# MouseSensor.net
KiCad netlist of a schematic drawn in Altium Designer
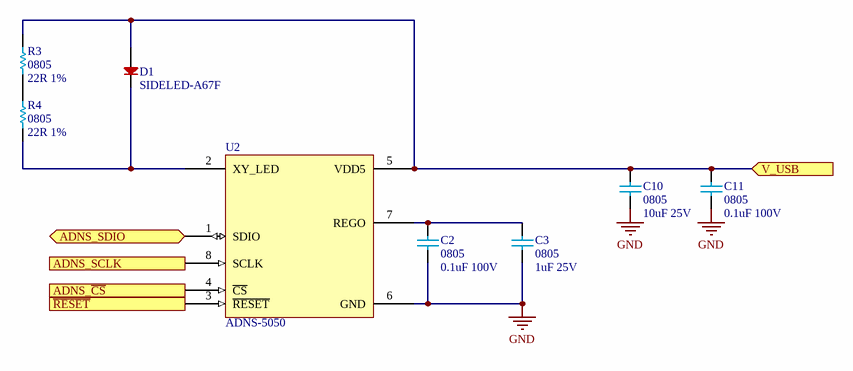
[diagram p0: MouseSensor.SchDoc]

(export (version "E")
  (design (tool "Eeschema 10.0.6"))
  (components
    (comp (ref "C2")
      (value "0805")
      (footprint "0805 - TALL")
      (description "0805, X5R or better")
      (fields (field (name "ALTIUM_VALUE") "0.1uF 100V"))
      (libsource (lib "Chip_Passives") (part "Cap 0.1uF 100V"))
    )
    (comp (ref "C3")
      (value "0805")
      (footprint "0805 - TALL")
      (description "0805, X5R or better")
      (fields (field (name "ALTIUM_VALUE") "1uF 25V"))
      (libsource (lib "Chip_Passives") (part "Cap 1uF 25V"))
    )
    (comp (ref "C10")
      (value "0805")
      (footprint "0805 - TALL")
      (description "0805, X5R or better")
      (fields (field (name "ALTIUM_VALUE") "10uF 25V"))
      (libsource (lib "Chip_Passives") (part "Cap 10uF 25V"))
    )
    (comp (ref "C11")
      (value "0805")
      (footprint "0805 - TALL")
      (description "0805, X5R or better")
      (fields (field (name "ALTIUM_VALUE") "0.1uF 100V"))
      (libsource (lib "Chip_Passives") (part "Cap 0.1uF 100V"))
    )
    (comp (ref "D1")
      (value "SIDELED-A67F")
      (footprint "SIDELED-A67F")
      (description "Red/Orange/Yellow Side-facing SMT LEDs, high brightness (~2lm)")
      (libsource (lib "LEDs") (part "SIDELED-A67F"))
    )
    (comp (ref "R3")
      (value "0805")
      (footprint "0805")
      (description "Chip resistor")
      (fields (field (name "ALTIUM_VALUE") "22R 1%"))
      (libsource (lib "Chip_Passives") (part "Res 22R 1% 0805"))
    )
    (comp (ref "R4")
      (value "0805")
      (footprint "0805")
      (description "Chip resistor")
      (fields (field (name "ALTIUM_VALUE") "22R 1%"))
      (libsource (lib "Chip_Passives") (part "Res 22R 1% 0805"))
    )
    (comp (ref "U2")
      (value "ADNS-5050")
      (footprint "ADNS-5050")
      (description "Optical Mouse Navigation Sensor")
      (libsource (lib "OptoElectronics") (part "ADNS-5050"))
    )
  )
  (nets
    (net (code "1") (name "/ADNS_SCLK") (class "Default")
      (node (ref "U2") (pin "8") (pinfunction "SCLK_8") (pintype "input"))
    )
    (net (code "2") (name "/ADNS_SDIO") (class "Default")
      (node (ref "U2") (pin "1") (pinfunction "SDIO_1") (pintype "bidirectional"))
    )
    (net (code "3") (name "/ADNS_~{CS}") (class "Default")
      (node (ref "U2") (pin "4") (pinfunction "~{CS}_4") (pintype "input"))
    )
    (net (code "4") (name "/V_USB") (class "Default")
      (node (ref "C10") (pin "2") (pinfunction "2_2") (pintype "passive"))
      (node (ref "C11") (pin "2") (pinfunction "2_2") (pintype "passive"))
      (node (ref "D1") (pin "A") (pinfunction "A_A") (pintype "passive"))
      (node (ref "R3") (pin "2") (pinfunction "2_2") (pintype "passive"))
      (node (ref "U2") (pin "5") (pinfunction "VDD5_5") (pintype "power_in"))
    )
    (net (code "5") (name "/~{RESET}") (class "Default")
      (node (ref "U2") (pin "3") (pinfunction "~{RESET}_3") (pintype "input"))
    )
    (net (code "6") (name "GND") (class "Default")
      (node (ref "C10") (pin "1") (pinfunction "1_1") (pintype "passive"))
      (node (ref "C11") (pin "1") (pinfunction "1_1") (pintype "passive"))
      (node (ref "C2") (pin "1") (pinfunction "1_1") (pintype "passive"))
      (node (ref "C3") (pin "1") (pinfunction "1_1") (pintype "passive"))
      (node (ref "U2") (pin "6") (pinfunction "GND_6") (pintype "passive"))
    )
    (net (code "7") (name "Net-(R3-Pad1)") (class "Default")
      (node (ref "R3") (pin "1") (pinfunction "1_1") (pintype "passive"))
      (node (ref "R4") (pin "2") (pinfunction "2_2") (pintype "passive"))
    )
    (net (code "8") (name "Net-(U2-REGO)") (class "Default")
      (node (ref "C2") (pin "2") (pinfunction "2_2") (pintype "passive"))
      (node (ref "C3") (pin "2") (pinfunction "2_2") (pintype "passive"))
      (node (ref "U2") (pin "7") (pinfunction "REGO_7") (pintype "power_in"))
    )
    (net (code "9") (name "Net-(U2-XY_LED)") (class "Default")
      (node (ref "D1") (pin "C") (pinfunction "C_C") (pintype "passive"))
      (node (ref "R4") (pin "1") (pinfunction "1_1") (pintype "passive"))
      (node (ref "U2") (pin "2") (pinfunction "XY_LED_2") (pintype "open_collector"))
    )
  )
)
